# Dormio_nrf52.net
KiCad netlist of a schematic drawn in Altium Designer
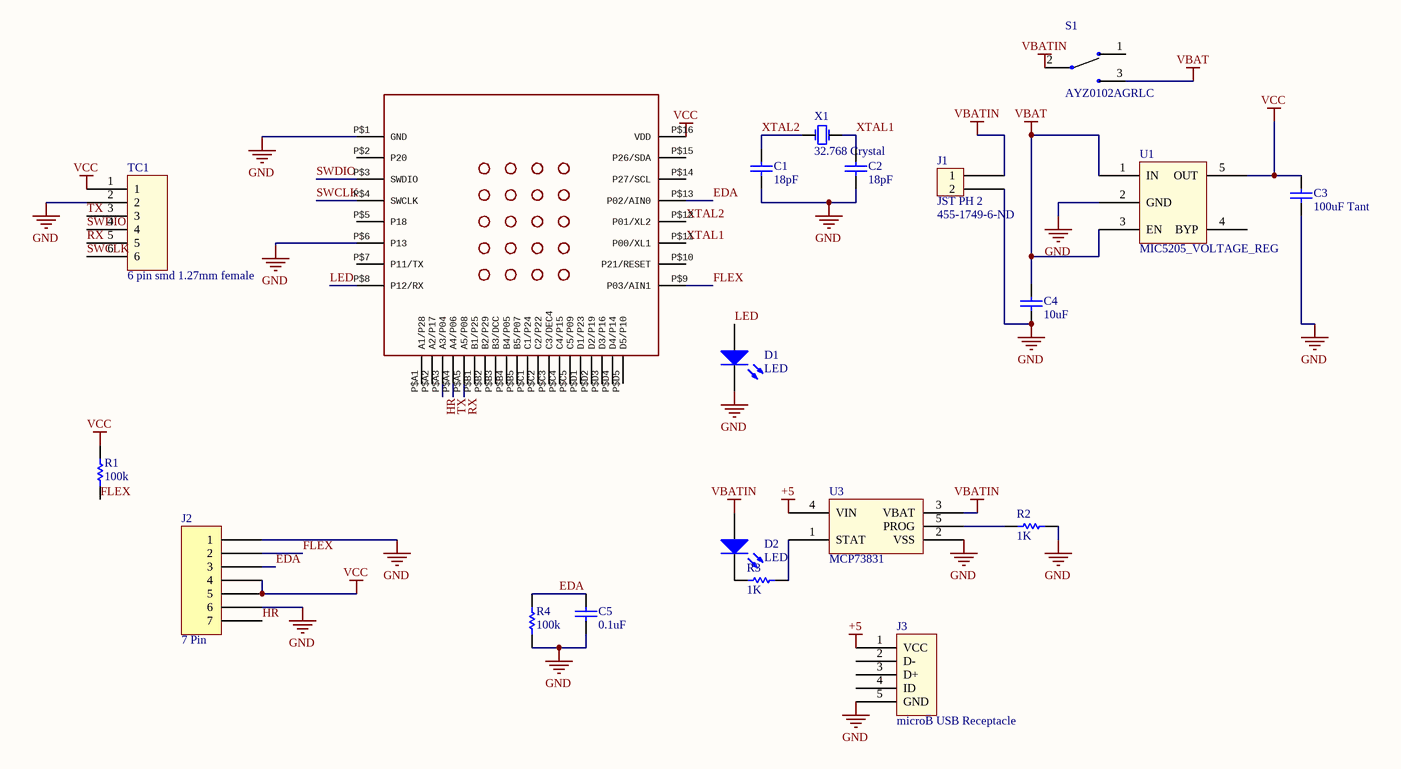
[diagram p0: Dormio_nrf52.SchDoc]

(export (version "E")
  (design (tool "Eeschema 10.0.6"))
  (components
    (comp (ref "C1")
      (value "18pF")
      (footprint "0603W")
      (description "SMD Cap 0603")
      (libsource (lib "Artem_Library") (part "Capacitor"))
    )
    (comp (ref "C2")
      (value "18pF")
      (footprint "0603W")
      (description "SMD Cap 0603")
      (libsource (lib "Artem_Library") (part "Capacitor"))
    )
    (comp (ref "C3")
      (value "100uF Tant")
      (footprint "0603W")
      (description "SMD Cap 1206")
      (libsource (lib "Artem_Library") (part "Capacitor"))
    )
    (comp (ref "C4")
      (value "10uF")
      (footprint "0603W")
      (description "SMD Cap 1206")
      (libsource (lib "Artem_Library") (part "Capacitor"))
    )
    (comp (ref "C5")
      (value "0.1uF")
      (footprint "0603W")
      (description "SMD Cap 1206")
      (libsource (lib "Artem_Library") (part "Capacitor"))
    )
    (comp (ref "D1")
      (value "LED")
      (footprint "0603 LED")
      (description "LED SMD 1206/0603")
      (libsource (lib "Artem_Library") (part "LED"))
    )
    (comp (ref "D2")
      (value "LED")
      (footprint "0603 LED")
      (description "LED SMD 1206/0603")
      (libsource (lib "Artem_Library") (part "LED"))
    )
    (comp (ref "J1")
      (value "JST PH 2")
      (footprint "JST PH 2")
      (fields (field (name "SUPPLIER PART NUMBER 1") "455-1749-6-ND"))
      (libsource (lib "Artem_Library") (part "JST PH 2"))
    )
    (comp (ref "J2")
      (value "7 Pin")
      (footprint "JST SM07B-GHS-TB")
      (libsource (lib "Connectors") (part "7 Pin"))
    )
    (comp (ref "J3")
      (value "microB USB Receptacle")
      (footprint "MicroB USB Standarad SMT")
      (fields (field (name "MANUFACTURER") "ZX62-B-5PA(11)"))
      (libsource (lib "Artem_Library") (part "microB USB Receptacle"))
    )
    (comp (ref "R1") (value "100k") (footprint "0603W") (libsource (lib "Artem_Library") (part "Resistor")))
    (comp (ref "R2") (value "1K") (footprint "0603W") (libsource (lib "Artem_Library") (part "Resistor")))
    (comp (ref "R3") (value "1K") (footprint "0603W") (libsource (lib "Artem_Library") (part "Resistor")))
    (comp (ref "R4") (value "100k") (footprint "0603W") (libsource (lib "Artem_Library") (part "Resistor")))
    (comp (ref "S1")
      (value "AYZ0102AGRLC")
      (footprint "*SW_AYZ0102AGRLC")
      (description "Switch Slide ON ON SPDT Side Slide 0.1A 12VDC 1.2VA 10000Cycles Gull Wing SMD T/R")
      (fields (field (name "MF") "C&K"))
      (libsource (lib "AYZ0102AGRLC") (part "AYZ0102AGRLC"))
    )
    (comp (ref "TC1")
      (value "6 pin smd 1.27mm female")
      (footprint "TC2030-IDC-NL")
      (libsource (lib "Artem_Library") (part "6 pin smd 1.27mm female"))
    )
    (comp (ref "U1")
      (value "MIC5205_VOLTAGE_REG")
      (footprint "SOT-23-5")
      (description "5V LDO SMD")
      (libsource (lib "Artem_Library") (part "MIC5205_VOLTAGE_REG"))
    )
    (comp (ref "U2")
      (value "B3 DCC ,C3 DEC4 for power saving , 10uH , 15nH")
      (footprint "BC832")
      (libsource (lib "BC832") (part "BC832-V1"))
    )
    (comp (ref "U3")
      (value "MCP73831")
      (footprint "SOT-23-5")
      (description "IC CONTROLLR LI-ION 4.2V SOT23-5")
      (fields (field (name "MANUFACTURER") "MCP73831T-2ACI/OT"))
      (libsource (lib "Artem_Library") (part "MCP73831"))
    )
    (comp (ref "X1")
      (value "32.768 Crystal")
      (footprint "32.768 Crystal")
      (libsource (lib "Artem_Library") (part "32.768 Crystal"))
    )
  )
  (nets
    (net (code "1") (name "+5") (class "Default")
      (node (ref "J3") (pin "1") (pinfunction "VCC_1") (pintype "passive"))
      (node (ref "U3") (pin "4") (pinfunction "VIN_4") (pintype "passive"))
    )
    (net (code "2") (name "/EDA") (class "Default")
      (node (ref "C5") (pin "1") (pinfunction "1_1") (pintype "passive"))
      (node (ref "J2") (pin "3") (pinfunction "3_3") (pintype "passive"))
      (node (ref "R4") (pin "2") (pinfunction "2_2") (pintype "passive"))
      (node (ref "U2") (pin "P$13") (pinfunction "P02/AIN0_P$13") (pintype "passive"))
    )
    (net (code "3") (name "/FLEX") (class "Default")
      (node (ref "J2") (pin "2") (pinfunction "2_2") (pintype "passive"))
      (node (ref "R1") (pin "1") (pinfunction "1_1") (pintype "passive"))
      (node (ref "U2") (pin "P$9") (pinfunction "P03/AIN1_P$9") (pintype "passive"))
    )
    (net (code "4") (name "/HR") (class "Default")
      (node (ref "J2") (pin "7") (pinfunction "7_7") (pintype "passive"))
      (node (ref "U2") (pin "P$A3") (pinfunction "A3/P04_P$A3") (pintype "passive"))
    )
    (net (code "5") (name "/LED") (class "Default")
      (node (ref "D1") (pin "1") (pinfunction "A_1") (pintype "passive"))
      (node (ref "U2") (pin "P$8") (pinfunction "P12/RX_P$8") (pintype "passive"))
    )
    (net (code "6") (name "/RX") (class "Default")
      (node (ref "TC1") (pin "5") (pinfunction "5_5") (pintype "passive"))
      (node (ref "U2") (pin "P$A5") (pinfunction "A5/P08_P$A5") (pintype "passive"))
    )
    (net (code "7") (name "/SWCLK") (class "Default")
      (node (ref "TC1") (pin "6") (pinfunction "6_6") (pintype "passive"))
      (node (ref "U2") (pin "P$4") (pinfunction "SWCLK_P$4") (pintype "passive"))
    )
    (net (code "8") (name "/SWDIO") (class "Default")
      (node (ref "TC1") (pin "4") (pinfunction "4_4") (pintype "passive"))
      (node (ref "U2") (pin "P$3") (pinfunction "SWDIO_P$3") (pintype "passive"))
    )
    (net (code "9") (name "/TX") (class "Default")
      (node (ref "TC1") (pin "3") (pinfunction "3_3") (pintype "passive"))
      (node (ref "U2") (pin "P$A4") (pinfunction "A4/P06_P$A4") (pintype "passive"))
    )
    (net (code "10") (name "/XTAL1") (class "Default")
      (node (ref "C2") (pin "2") (pinfunction "2_2") (pintype "passive"))
      (node (ref "U2") (pin "P$11") (pinfunction "P00/XL1_P$11") (pintype "passive"))
      (node (ref "X1") (pin "2") (pinfunction "2_2") (pintype "passive"))
    )
    (net (code "11") (name "/XTAL2") (class "Default")
      (node (ref "C1") (pin "1") (pinfunction "1_1") (pintype "passive"))
      (node (ref "U2") (pin "P$12") (pinfunction "P01/XL2_P$12") (pintype "passive"))
      (node (ref "X1") (pin "1") (pinfunction "1_1") (pintype "passive"))
    )
    (net (code "12") (name "GND") (class "Default")
      (node (ref "C1") (pin "2") (pinfunction "2_2") (pintype "passive"))
      (node (ref "C2") (pin "1") (pinfunction "1_1") (pintype "passive"))
      (node (ref "C3") (pin "2") (pinfunction "2_2") (pintype "passive"))
      (node (ref "C4") (pin "2") (pinfunction "2_2") (pintype "passive"))
      (node (ref "C5") (pin "2") (pinfunction "2_2") (pintype "passive"))
      (node (ref "D1") (pin "2") (pinfunction "K_2") (pintype "passive"))
      (node (ref "J1") (pin "2") (pinfunction "2_2") (pintype "passive"))
      (node (ref "J2") (pin "1") (pinfunction "1_1") (pintype "passive"))
      (node (ref "J2") (pin "6") (pinfunction "6_6") (pintype "passive"))
      (node (ref "J3") (pin "5") (pinfunction "GND_5") (pintype "passive"))
      (node (ref "R2") (pin "2") (pinfunction "2_2") (pintype "passive"))
      (node (ref "R4") (pin "1") (pinfunction "1_1") (pintype "passive"))
      (node (ref "TC1") (pin "2") (pinfunction "2_2") (pintype "passive"))
      (node (ref "U1") (pin "2") (pinfunction "GND_2") (pintype "passive"))
      (node (ref "U2") (pin "P$1") (pinfunction "GND_P$1") (pintype "passive"))
      (node (ref "U2") (pin "P$6") (pinfunction "P13_P$6") (pintype "passive"))
      (node (ref "U3") (pin "2") (pinfunction "VSS_2") (pintype "passive"))
    )
    (net (code "13") (name "Net-(D2-K)") (class "Default")
      (node (ref "D2") (pin "2") (pinfunction "K_2") (pintype "passive"))
      (node (ref "R3") (pin "1") (pinfunction "1_1") (pintype "passive"))
    )
    (net (code "14") (name "Net-(U3-PROG)") (class "Default")
      (node (ref "R2") (pin "1") (pinfunction "1_1") (pintype "passive"))
      (node (ref "U3") (pin "5") (pinfunction "PROG_5") (pintype "passive"))
    )
    (net (code "15") (name "Net-(U3-STAT)") (class "Default")
      (node (ref "R3") (pin "2") (pinfunction "2_2") (pintype "passive"))
      (node (ref "U3") (pin "1") (pinfunction "STAT_1") (pintype "passive"))
    )
    (net (code "16") (name "VBAT") (class "Default")
      (node (ref "C4") (pin "1") (pinfunction "1_1") (pintype "passive"))
      (node (ref "S1") (pin "3") (pinfunction "3_3") (pintype "passive"))
      (node (ref "U1") (pin "1") (pinfunction "IN_1") (pintype "passive"))
      (node (ref "U1") (pin "3") (pinfunction "EN_3") (pintype "passive"))
    )
    (net (code "17") (name "VBATIN") (class "Default")
      (node (ref "D2") (pin "1") (pinfunction "A_1") (pintype "passive"))
      (node (ref "J1") (pin "1") (pinfunction "1_1") (pintype "passive"))
      (node (ref "S1") (pin "2") (pinfunction "2_2") (pintype "passive"))
      (node (ref "U3") (pin "3") (pinfunction "VBAT_3") (pintype "passive"))
    )
    (net (code "18") (name "VCC") (class "Default")
      (node (ref "C3") (pin "1") (pinfunction "1_1") (pintype "passive"))
      (node (ref "J2") (pin "4") (pinfunction "4_4") (pintype "passive"))
      (node (ref "J2") (pin "5") (pinfunction "5_5") (pintype "passive"))
      (node (ref "R1") (pin "2") (pinfunction "2_2") (pintype "passive"))
      (node (ref "TC1") (pin "1") (pinfunction "1_1") (pintype "passive"))
      (node (ref "U1") (pin "5") (pinfunction "OUT_5") (pintype "passive"))
      (node (ref "U2") (pin "P$16") (pinfunction "VDD_P$16") (pintype "passive"))
    )
    (net (code "19") (name "unconnected-(J3-D+-Pad3)") (class "Default")
      (node (ref "J3") (pin "3") (pinfunction "D+_3") (pintype "passive"))
    )
    (net (code "20") (name "unconnected-(J3-D--Pad2)") (class "Default")
      (node (ref "J3") (pin "2") (pinfunction "D-_2") (pintype "passive"))
    )
    (net (code "21") (name "unconnected-(J3-ID-Pad4)") (class "Default")
      (node (ref "J3") (pin "4") (pinfunction "ID_4") (pintype "passive"))
    )
    (net (code "22") (name "unconnected-(S1-Pad1)") (class "Default")
      (node (ref "S1") (pin "1") (pinfunction "1_1") (pintype "passive"))
    )
    (net (code "23") (name "unconnected-(U1-BYP-Pad4)") (class "Default")
      (node (ref "U1") (pin "4") (pinfunction "BYP_4") (pintype "passive"))
    )
    (net (code "24") (name "unconnected-(U2-A1{slash}P28-PadP$A1)") (class "Default")
      (node (ref "U2") (pin "P$A1") (pinfunction "A1/P28_P$A1") (pintype "passive"))
    )
    (net (code "25") (name "unconnected-(U2-A2{slash}P17-PadP$A2)") (class "Default")
      (node (ref "U2") (pin "P$A2") (pinfunction "A2/P17_P$A2") (pintype "passive"))
    )
    (net (code "26") (name "unconnected-(U2-B1{slash}P25-PadP$B1)") (class "Default")
      (node (ref "U2") (pin "P$B1") (pinfunction "B1/P25_P$B1") (pintype "passive"))
    )
    (net (code "27") (name "unconnected-(U2-B2{slash}P29-PadP$B2)") (class "Default")
      (node (ref "U2") (pin "P$B2") (pinfunction "B2/P29_P$B2") (pintype "passive"))
    )
    (net (code "28") (name "unconnected-(U2-B3{slash}DCC-PadP$B3)") (class "Default")
      (node (ref "U2") (pin "P$B3") (pinfunction "B3/DCC_P$B3") (pintype "passive"))
    )
    (net (code "29") (name "unconnected-(U2-B4{slash}P05-PadP$B4)") (class "Default")
      (node (ref "U2") (pin "P$B4") (pinfunction "B4/P05_P$B4") (pintype "passive"))
    )
    (net (code "30") (name "unconnected-(U2-B5{slash}P07-PadP$B5)") (class "Default")
      (node (ref "U2") (pin "P$B5") (pinfunction "B5/P07_P$B5") (pintype "passive"))
    )
    (net (code "31") (name "unconnected-(U2-C1{slash}P24-PadP$C1)") (class "Default")
      (node (ref "U2") (pin "P$C1") (pinfunction "C1/P24_P$C1") (pintype "passive"))
    )
    (net (code "32") (name "unconnected-(U2-C2{slash}P22-PadP$C2)") (class "Default")
      (node (ref "U2") (pin "P$C2") (pinfunction "C2/P22_P$C2") (pintype "passive"))
    )
    (net (code "33") (name "unconnected-(U2-C3{slash}DEC4-PadP$C3)") (class "Default")
      (node (ref "U2") (pin "P$C3") (pinfunction "C3/DEC4_P$C3") (pintype "passive"))
    )
    (net (code "34") (name "unconnected-(U2-C4{slash}P15-PadP$C4)") (class "Default")
      (node (ref "U2") (pin "P$C4") (pinfunction "C4/P15_P$C4") (pintype "passive"))
    )
    (net (code "35") (name "unconnected-(U2-C5{slash}P09-PadP$C5)") (class "Default")
      (node (ref "U2") (pin "P$C5") (pinfunction "C5/P09_P$C5") (pintype "passive"))
    )
    (net (code "36") (name "unconnected-(U2-D1{slash}P23-PadP$D1)") (class "Default")
      (node (ref "U2") (pin "P$D1") (pinfunction "D1/P23_P$D1") (pintype "passive"))
    )
    (net (code "37") (name "unconnected-(U2-D2{slash}P19-PadP$D2)") (class "Default")
      (node (ref "U2") (pin "P$D2") (pinfunction "D2/P19_P$D2") (pintype "passive"))
    )
    (net (code "38") (name "unconnected-(U2-D3{slash}P16-PadP$D3)") (class "Default")
      (node (ref "U2") (pin "P$D3") (pinfunction "D3/P16_P$D3") (pintype "passive"))
    )
    (net (code "39") (name "unconnected-(U2-D4{slash}P14-PadP$D4)") (class "Default")
      (node (ref "U2") (pin "P$D4") (pinfunction "D4/P14_P$D4") (pintype "passive"))
    )
    (net (code "40") (name "unconnected-(U2-D5{slash}P10-PadP$D5)") (class "Default")
      (node (ref "U2") (pin "P$D5") (pinfunction "D5/P10_P$D5") (pintype "passive"))
    )
    (net (code "41") (name "unconnected-(U2-P11{slash}TX-PadP$7)") (class "Default")
      (node (ref "U2") (pin "P$7") (pinfunction "P11/TX_P$7") (pintype "passive"))
    )
    (net (code "42") (name "unconnected-(U2-P18-PadP$5)") (class "Default")
      (node (ref "U2") (pin "P$5") (pinfunction "P18_P$5") (pintype "passive"))
    )
    (net (code "43") (name "unconnected-(U2-P20-PadP$2)") (class "Default")
      (node (ref "U2") (pin "P$2") (pinfunction "P20_P$2") (pintype "passive"))
    )
    (net (code "44") (name "unconnected-(U2-P21{slash}RESET-PadP$10)") (class "Default")
      (node (ref "U2") (pin "P$10") (pinfunction "P21/RESET_P$10") (pintype "passive"))
    )
    (net (code "45") (name "unconnected-(U2-P26{slash}SDA-PadP$15)") (class "Default")
      (node (ref "U2") (pin "P$15") (pinfunction "P26/SDA_P$15") (pintype "passive"))
    )
    (net (code "46") (name "unconnected-(U2-P27{slash}SCL-PadP$14)") (class "Default")
      (node (ref "U2") (pin "P$14") (pinfunction "P27/SCL_P$14") (pintype "passive"))
    )
  )
)
